# Level_Shifter.net
KiCad netlist of a schematic drawn in Altium Designer
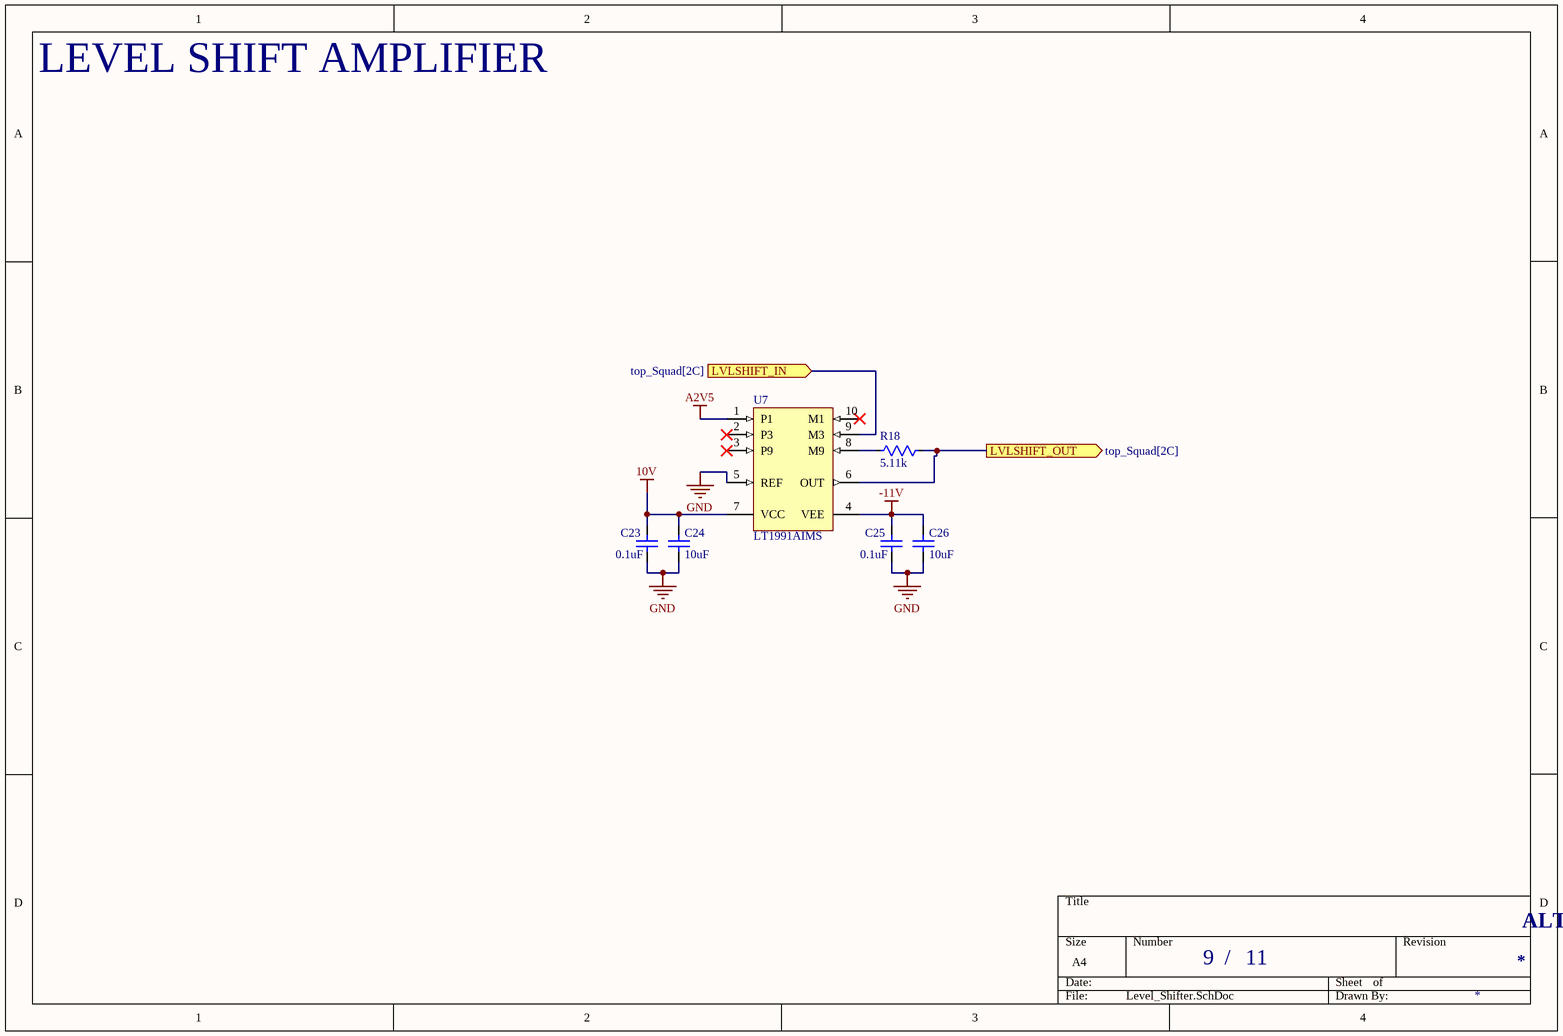
[diagram p0: Level_Shifter.SchDoc]

(export (version "E")
  (design (tool "Eeschema 10.0.6"))
  (components
    (comp (ref "C23")
      (value "0.1uF")
      (footprint "CAP 0603 NON-IPC KEMET X7R")
      (description "Kemet C0603C104K5RACAUTO - Cap Ceramic 0.1uF 50V X7R 10% 0603 125C Paper T/R")
      (fields (field (name "MF") "Kemet") (field (name "MP") "C0603C104K5RACAUTO"))
      (libsource (lib "ALTAIR_PD_Capacitors") (part "CAP"))
    )
    (comp (ref "C24")
      (value "10uF")
      (footprint "CAP 0805 IPC MID DENSITY")
      (description "Murata GRM21BR61E106KA73L - Cap Ceramic 10uF 10% 25V X5R 0805")
      (fields (field (name "MF") "Murata") (field (name "MP") "GRM21BR61E106KA73L"))
      (libsource (lib "ALTAIR_PD_Capacitors") (part "CAP"))
    )
    (comp (ref "C25")
      (value "0.1uF")
      (footprint "CAP 0603 NON-IPC KEMET X7R")
      (description "Kemet C0603C104K5RACAUTO - Cap Ceramic 0.1uF 50V X7R 10% 0603 125C Paper T/R")
      (fields (field (name "MF") "Kemet") (field (name "MP") "C0603C104K5RACAUTO"))
      (libsource (lib "ALTAIR_PD_Capacitors") (part "CAP"))
    )
    (comp (ref "C26")
      (value "10uF")
      (footprint "CAP 0805 IPC MID DENSITY")
      (description "Murata GRM21BR61E106KA73L - Cap Ceramic 10uF 10% 25V X5R 0805")
      (fields (field (name "MF") "Murata") (field (name "MP") "GRM21BR61E106KA73L"))
      (libsource (lib "ALTAIR_PD_Capacitors") (part "CAP"))
    )
    (comp (ref "R18")
      (value "5.11k")
      (footprint "RES 0402 IPC MID DENSITY")
      (description "Panasonic ERA-2AEB5111X - Res 5.11k 0.1% 1/16W SMD 0402")
      (fields (field (name "MF") "Panasonic Electronic Components") (field (name "MP") "ERA-2AEB5111X"))
      (libsource (lib "ALTAIR_PD_Resistors") (part "RES"))
    )
    (comp (ref "U7")
      (value "LT1991AIMS")
      (footprint "10-SOP 0.5MM PITCH 3MM WIDTH IPC HIGH DENSITY")
      (fields
        (field (name "MF") "Linear Technology")
        (field (name "MP") "LT1991AIMS#PBF")
        (field (name "LINEAR TECHNOLOGY PART NUMBER") "LT1991")
      )
      (libsource (lib "ALTAIR_PD_Amplifiers") (part "LT1991IMS#TRPBF"))
    )
  )
  (nets
    (net (code "1") (name "-11V") (class "Default")
      (node (ref "C25") (pin "2") (pinfunction "2_2") (pintype "passive"))
      (node (ref "C26") (pin "2") (pinfunction "2_2") (pintype "passive"))
      (node (ref "U7") (pin "4") (pinfunction "VEE_4") (pintype "power_in"))
    )
    (net (code "2") (name "/LVLSHIFT_IN") (class "Default")
      (node (ref "U7") (pin "9") (pinfunction "M3_9") (pintype "input"))
    )
    (net (code "3") (name "/LVLSHIFT_OUT") (class "Default")
      (node (ref "R18") (pin "2") (pinfunction "2_2") (pintype "passive"))
      (node (ref "U7") (pin "6") (pinfunction "OUT_6") (pintype "output"))
    )
    (net (code "4") (name "10V") (class "Default")
      (node (ref "C23") (pin "2") (pinfunction "2_2") (pintype "passive"))
      (node (ref "C24") (pin "2") (pinfunction "2_2") (pintype "passive"))
      (node (ref "U7") (pin "7") (pinfunction "VCC_7") (pintype "power_in"))
    )
    (net (code "5") (name "A2V5") (class "Default")
      (node (ref "U7") (pin "1") (pinfunction "P1_1") (pintype "input"))
    )
    (net (code "6") (name "GND") (class "Default")
      (node (ref "C23") (pin "1") (pinfunction "1_1") (pintype "passive"))
      (node (ref "C24") (pin "1") (pinfunction "1_1") (pintype "passive"))
      (node (ref "C25") (pin "1") (pinfunction "1_1") (pintype "passive"))
      (node (ref "C26") (pin "1") (pinfunction "1_1") (pintype "passive"))
      (node (ref "U7") (pin "5") (pinfunction "REF_5") (pintype "input"))
    )
    (net (code "7") (name "Net-(U7-M9)") (class "Default")
      (node (ref "R18") (pin "1") (pinfunction "1_1") (pintype "passive"))
      (node (ref "U7") (pin "8") (pinfunction "M9_8") (pintype "input"))
    )
    (net (code "8") (name "unconnected-(U7-M1-Pad10)") (class "Default")
      (node (ref "U7") (pin "10") (pinfunction "M1_10") (pintype "input+no_connect"))
    )
    (net (code "9") (name "unconnected-(U7-P3-Pad2)") (class "Default")
      (node (ref "U7") (pin "2") (pinfunction "P3_2") (pintype "input+no_connect"))
    )
    (net (code "10") (name "unconnected-(U7-P9-Pad3)") (class "Default")
      (node (ref "U7") (pin "3") (pinfunction "P9_3") (pintype "input+no_connect"))
    )
  )
)
